# 4_cyber60-mx_power.net
KiCad netlist of a schematic drawn in Altium Designer
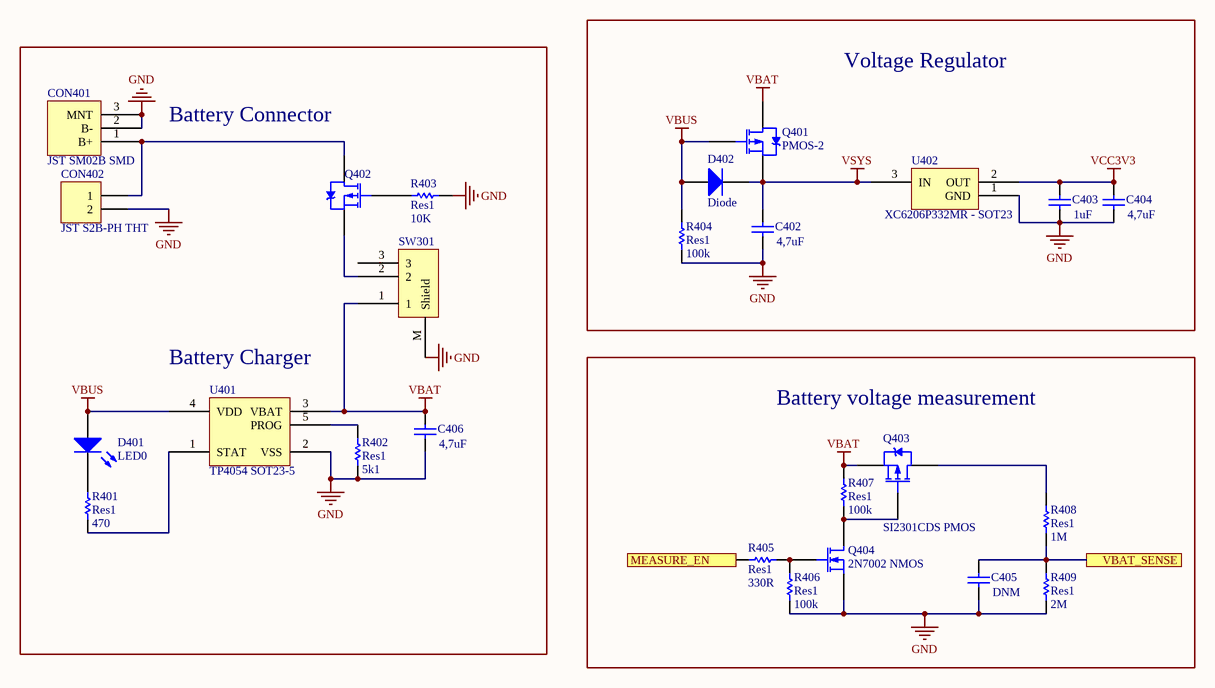
[diagram p0: 4_cyber60-mx_power.SchDoc]

(export (version "E")
  (design (tool "Eeschema 10.0.6"))
  (components
    (comp (ref "C402")
      (value "4,7uF")
      (footprint "C0603[1608]")
      (description "Capacitor")
      (fields (field (name "LCSC PART #") "C19666") (field (name "MRF.PART") "CL10A475KO8NNNC"))
      (libsource (lib "Miscellaneous Devices") (part "Cap"))
    )
    (comp (ref "C403")
      (value "1uF")
      (footprint "C0603[1608]")
      (description "Capacitor")
      (fields (field (name "MFG") "KEMET") (field (name "LCSC PART #") "C15849"))
      (libsource (lib "Miscellaneous Devices") (part "Cap"))
    )
    (comp (ref "C404")
      (value "4,7uF")
      (footprint "C0603[1608]")
      (description "Capacitor")
      (fields (field (name "LCSC PART #") "C19666") (field (name "MRF.PART") "CL10A475KO8NNNC"))
      (libsource (lib "Miscellaneous Devices") (part "Cap"))
    )
    (comp (ref "C405")
      (value "DNM")
      (footprint "C0603[1608]")
      (description "Capacitor")
      (libsource (lib "Miscellaneous Devices") (part "Cap"))
    )
    (comp (ref "C406")
      (value "4,7uF")
      (footprint "C0603[1608]")
      (description "Capacitor")
      (fields (field (name "LCSC PART #") "C19666") (field (name "MRF.PART") "CL10A475KO8NNNC"))
      (libsource (lib "Miscellaneous Devices") (part "Cap"))
    )
    (comp (ref "CON401")
      (value "JST SM02B SMD")
      (footprint "JST SM02B-SRSS-TB")
      (fields (field (name "LCSC PART #") "C160402") (field (name "MRF.PART") "SM02B-SRSS-TB(LF)(SN)"))
      (libsource (lib "Keebs") (part "JST S2B-PH-SM4-TB"))
    )
    (comp (ref "CON402")
      (value "JST S2B-PH THT")
      (footprint "Keebs:JST S2B-PH-K(LF)(SN)")
      (description "Header, 2-Pin")
      (fields (field (name "LCSC PART #") "C265016") (field (name "MRF.PART") "S2B-PH-K(LF)(SN)"))
      (libsource (lib "Miscellaneous Connectors") (part "Header 2"))
    )
    (comp (ref "D401")
      (value "LED0")
      (footprint "LED0603[1608]")
      (description "Typical INFRARED GaAs LED")
      (fields (field (name "LCSC PART #") "C72038") (field (name "MRF.PART") "19-213/Y2C-CQ2R2L/3T(CY)"))
      (libsource (lib "Miscellaneous Devices") (part "LED0"))
    )
    (comp (ref "D402")
      (value "Diode")
      (footprint "SOD-123")
      (description "Default Diode")
      (fields (field (name "LCSC PART #") "C8598") (field (name "MRF.PART") "B5819W"))
      (libsource (lib "Miscellaneous Devices") (part "Diode"))
    )
    (comp (ref "Q401")
      (value "PMOS-2")
      (footprint "SOT-23-3")
      (description "P-Channel Power MOSFET")
      (fields (field (name "MRF.PART") "SI2301CDS-T1-GE3") (field (name "LCSC PART #") "C10487"))
      (libsource (lib "Miscellaneous Devices") (part "PMOS-2"))
    )
    (comp (ref "Q402")
      (value "PMOS-2")
      (footprint "SOT-23-3")
      (description "P-Channel Power MOSFET")
      (fields (field (name "LCSC PART #") "C10487") (field (name "MRF.PART") "SI2301CDS-T1-GE3"))
      (libsource (lib "Miscellaneous Devices") (part "PMOS-2"))
    )
    (comp (ref "Q403")
      (value "SI2301CDS PMOS")
      (footprint "SOT-23-3")
      (description "P-Channel Power MOSFET")
      (fields (field (name "MRF.PART") "SI2301CDS-T1-GE3") (field (name "LCSC PART #") "C10487"))
      (libsource (lib "Miscellaneous Devices") (part "PMOS-2"))
    )
    (comp (ref "Q404")
      (value "2N7002 NMOS")
      (footprint "SOT-23-3")
      (description "N-Channel MOSFET")
      (fields (field (name "LCSC PART #") "C8545") (field (name "MRF.PART") "2N7002"))
      (libsource (lib "Miscellaneous Devices") (part "MOSFET-N"))
    )
    (comp (ref "R401")
      (value "Res1")
      (footprint "R0603[1608]")
      (description "Resistor")
      (fields
        (field (name "ALTIUM_VALUE") "470")
        (field (name "MFG") "Panasonic Electronic Components")
        (field (name "LCSC PART #") "C23179")
      )
      (libsource (lib "Miscellaneous Devices") (part "Res1"))
    )
    (comp (ref "R402")
      (value "Res1")
      (footprint "R0603[1608]")
      (description "Resistor")
      (fields
        (field (name "ALTIUM_VALUE") "5k1")
        (field (name "MFG") "Panasonic Electronic Components")
        (field (name "LCSC PART #") "C23186")
      )
      (libsource (lib "Miscellaneous Devices") (part "Res1"))
    )
    (comp (ref "R403")
      (value "Res1")
      (footprint "R0603[1608]")
      (description "Resistor")
      (fields
        (field (name "ALTIUM_VALUE") "10K")
        (field (name "MFG") "Panasonic Electronic Components")
        (field (name "LCSC PART #") "C25804")
      )
      (libsource (lib "Miscellaneous Devices") (part "Res1"))
    )
    (comp (ref "R404")
      (value "Res1")
      (footprint "R0603[1608]")
      (description "Resistor")
      (fields
        (field (name "ALTIUM_VALUE") "100k")
        (field (name "MRF.PART") "0603WAF1003T5E")
        (field (name "LCSC PART #") "C25803")
      )
      (libsource (lib "Miscellaneous Devices") (part "Res1"))
    )
    (comp (ref "R405")
      (value "Res1")
      (footprint "R0603[1608]")
      (description "Resistor")
      (fields
        (field (name "ALTIUM_VALUE") "330R")
        (field (name "LCSC PART #") "C23138")
        (field (name "MRF.PART") "0603WAF3300T5E")
      )
      (libsource (lib "Miscellaneous Devices") (part "Res1"))
    )
    (comp (ref "R406")
      (value "Res1")
      (footprint "R0603[1608]")
      (description "Resistor")
      (fields
        (field (name "ALTIUM_VALUE") "100k")
        (field (name "MRF.PART") "0603WAF1003T5E")
        (field (name "LCSC PART #") "C25803")
      )
      (libsource (lib "Miscellaneous Devices") (part "Res1"))
    )
    (comp (ref "R407")
      (value "Res1")
      (footprint "R0603[1608]")
      (description "Resistor")
      (fields
        (field (name "ALTIUM_VALUE") "100k")
        (field (name "MRF.PART") "0603WAF1003T5E")
        (field (name "LCSC PART #") "C25803")
      )
      (libsource (lib "Miscellaneous Devices") (part "Res1"))
    )
    (comp (ref "R408")
      (value "Res1")
      (footprint "R0603[1608]")
      (description "Resistor")
      (fields
        (field (name "ALTIUM_VALUE") "1M")
        (field (name "MRF.PART") "0603WAF1004T5E")
        (field (name "LCSC PART #") "C22935")
      )
      (libsource (lib "Miscellaneous Devices") (part "Res1"))
    )
    (comp (ref "R409")
      (value "Res1")
      (footprint "R0603[1608]")
      (description "Resistor")
      (fields
        (field (name "ALTIUM_VALUE") "2M")
        (field (name "MRF.PART") "0603WAF2004T5E")
        (field (name "LCSC PART #") "C22976")
      )
      (libsource (lib "Miscellaneous Devices") (part "Res1"))
    )
    (comp (ref "SW301")
      (value "Korean Hroparts Elec K3-1296S-E2")
      (footprint "Korean Hroparts Elec K3-1296S-E2")
      (fields (field (name "LCSC PART #") "C136659"))
      (libsource (lib "Keebs") (part "Korean Hroparts Elec K3-1296S-E2"))
    )
    (comp (ref "U401")
      (value "TP4054 SOT23-5")
      (footprint "SOT-23-5")
      (fields (field (name "LCSC PART #") "C32574") (field (name "MRF.PART") "TP4054"))
      (libsource (lib "Keebs") (part "MCP73831"))
    )
    (comp (ref "U402")
      (value "XC6206P332MR - SOT23")
      (footprint "SOT-23-3")
      (fields
        (field (name "LCSC PART #") "C5446")
        (field (name "MRF.PART") "XC6206P332MR")
        (field (name "MFG") "Texas Instruments")
      )
      (libsource (lib "Keebs") (part "SOT23 LDO"))
    )
  )
  (nets
    (net (code "1") (name "/MEASURE_EN") (class "Default")
      (node (ref "R405") (pin "1") (pinfunction "1_1") (pintype "passive"))
    )
    (net (code "2") (name "/VBAT_SENSE") (class "Default")
      (node (ref "C405") (pin "2") (pinfunction "2_2") (pintype "passive"))
      (node (ref "R408") (pin "2") (pinfunction "2_2") (pintype "passive"))
      (node (ref "R409") (pin "1") (pinfunction "1_1") (pintype "passive"))
    )
    (net (code "3") (name "GND") (class "Default")
      (node (ref "C402") (pin "1") (pinfunction "1_1") (pintype "passive"))
      (node (ref "C403") (pin "1") (pinfunction "1_1") (pintype "passive"))
      (node (ref "C404") (pin "1") (pinfunction "1_1") (pintype "passive"))
      (node (ref "C405") (pin "1") (pinfunction "1_1") (pintype "passive"))
      (node (ref "C406") (pin "1") (pinfunction "1_1") (pintype "passive"))
      (node (ref "CON401") (pin "2") (pinfunction "B-_2") (pintype "passive"))
      (node (ref "CON401") (pin "3") (pinfunction "MNT_3") (pintype "passive"))
      (node (ref "CON402") (pin "2") (pinfunction "2_2") (pintype "passive"))
      (node (ref "Q404") (pin "2") (pinfunction "S_2") (pintype "passive"))
      (node (ref "R402") (pin "2") (pinfunction "2_2") (pintype "passive"))
      (node (ref "R403") (pin "2") (pinfunction "2_2") (pintype "passive"))
      (node (ref "R404") (pin "2") (pinfunction "2_2") (pintype "passive"))
      (node (ref "R406") (pin "2") (pinfunction "2_2") (pintype "passive"))
      (node (ref "R409") (pin "2") (pinfunction "2_2") (pintype "passive"))
      (node (ref "SW301") (pin "M") (pinfunction "Shield_M") (pintype "passive"))
      (node (ref "U401") (pin "2") (pinfunction "VSS_2") (pintype "passive"))
      (node (ref "U402") (pin "1") (pinfunction "GND_1") (pintype "passive"))
    )
    (net (code "4") (name "Net-(CON401-B+)") (class "Default")
      (node (ref "CON401") (pin "1") (pinfunction "B+_1") (pintype "passive"))
      (node (ref "CON402") (pin "1") (pinfunction "1_1") (pintype "passive"))
      (node (ref "Q402") (pin "3") (pinfunction "D_3") (pintype "passive"))
    )
    (net (code "5") (name "Net-(D401-K)") (class "Default")
      (node (ref "D401") (pin "2") (pinfunction "K_2") (pintype "passive"))
      (node (ref "R401") (pin "2") (pinfunction "2_2") (pintype "passive"))
    )
    (net (code "6") (name "Net-(Q402-G)") (class "Default")
      (node (ref "Q402") (pin "1") (pinfunction "G_1") (pintype "passive"))
      (node (ref "R403") (pin "1") (pinfunction "1_1") (pintype "passive"))
    )
    (net (code "7") (name "Net-(Q402-S)") (class "Default")
      (node (ref "Q402") (pin "2") (pinfunction "S_2") (pintype "passive"))
      (node (ref "SW301") (pin "2") (pinfunction "2_2") (pintype "passive"))
    )
    (net (code "8") (name "Net-(Q403-D)") (class "Default")
      (node (ref "Q403") (pin "3") (pinfunction "D_3") (pintype "passive"))
      (node (ref "R408") (pin "1") (pinfunction "1_1") (pintype "passive"))
    )
    (net (code "9") (name "Net-(Q403-G)") (class "Default")
      (node (ref "Q403") (pin "1") (pinfunction "G_1") (pintype "passive"))
      (node (ref "Q404") (pin "3") (pinfunction "D_3") (pintype "passive"))
      (node (ref "R407") (pin "2") (pinfunction "2_2") (pintype "passive"))
    )
    (net (code "10") (name "Net-(Q404-G)") (class "Default")
      (node (ref "Q404") (pin "1") (pinfunction "G_1") (pintype "passive"))
      (node (ref "R405") (pin "2") (pinfunction "2_2") (pintype "passive"))
      (node (ref "R406") (pin "1") (pinfunction "1_1") (pintype "passive"))
    )
    (net (code "11") (name "Net-(U401-PROG)") (class "Default")
      (node (ref "R402") (pin "1") (pinfunction "1_1") (pintype "passive"))
      (node (ref "U401") (pin "5") (pinfunction "PROG_5") (pintype "passive"))
    )
    (net (code "12") (name "Net-(U401-STAT)") (class "Default")
      (node (ref "R401") (pin "1") (pinfunction "1_1") (pintype "passive"))
      (node (ref "U401") (pin "1") (pinfunction "STAT_1") (pintype "passive"))
    )
    (net (code "13") (name "VBAT") (class "Default")
      (node (ref "C406") (pin "2") (pinfunction "2_2") (pintype "passive"))
      (node (ref "Q401") (pin "3") (pinfunction "D_3") (pintype "passive"))
      (node (ref "Q403") (pin "2") (pinfunction "S_2") (pintype "passive"))
      (node (ref "R407") (pin "1") (pinfunction "1_1") (pintype "passive"))
      (node (ref "SW301") (pin "1") (pinfunction "1_1") (pintype "passive"))
      (node (ref "U401") (pin "3") (pinfunction "VBAT_3") (pintype "passive"))
    )
    (net (code "14") (name "VBUS") (class "Default")
      (node (ref "D401") (pin "1") (pinfunction "A_1") (pintype "passive"))
      (node (ref "D402") (pin "1") (pinfunction "A_1") (pintype "passive"))
      (node (ref "Q401") (pin "1") (pinfunction "G_1") (pintype "passive"))
      (node (ref "R404") (pin "1") (pinfunction "1_1") (pintype "passive"))
      (node (ref "U401") (pin "4") (pinfunction "VDD_4") (pintype "passive"))
    )
    (net (code "15") (name "VCC3V3") (class "Default")
      (node (ref "C403") (pin "2") (pinfunction "2_2") (pintype "passive"))
      (node (ref "C404") (pin "2") (pinfunction "2_2") (pintype "passive"))
      (node (ref "U402") (pin "2") (pinfunction "OUT_2") (pintype "passive"))
    )
    (net (code "16") (name "VSYS") (class "Default")
      (node (ref "C402") (pin "2") (pinfunction "2_2") (pintype "passive"))
      (node (ref "D402") (pin "2") (pinfunction "K_2") (pintype "passive"))
      (node (ref "Q401") (pin "2") (pinfunction "S_2") (pintype "passive"))
      (node (ref "U402") (pin "3") (pinfunction "IN_3") (pintype "passive"))
    )
    (net (code "17") (name "unconnected-(SW301-Pad3)") (class "Default")
      (node (ref "SW301") (pin "3") (pinfunction "3_3") (pintype "passive"))
    )
  )
)
